# tinyio.net
KiCad netlist of a schematic drawn in EAGLE
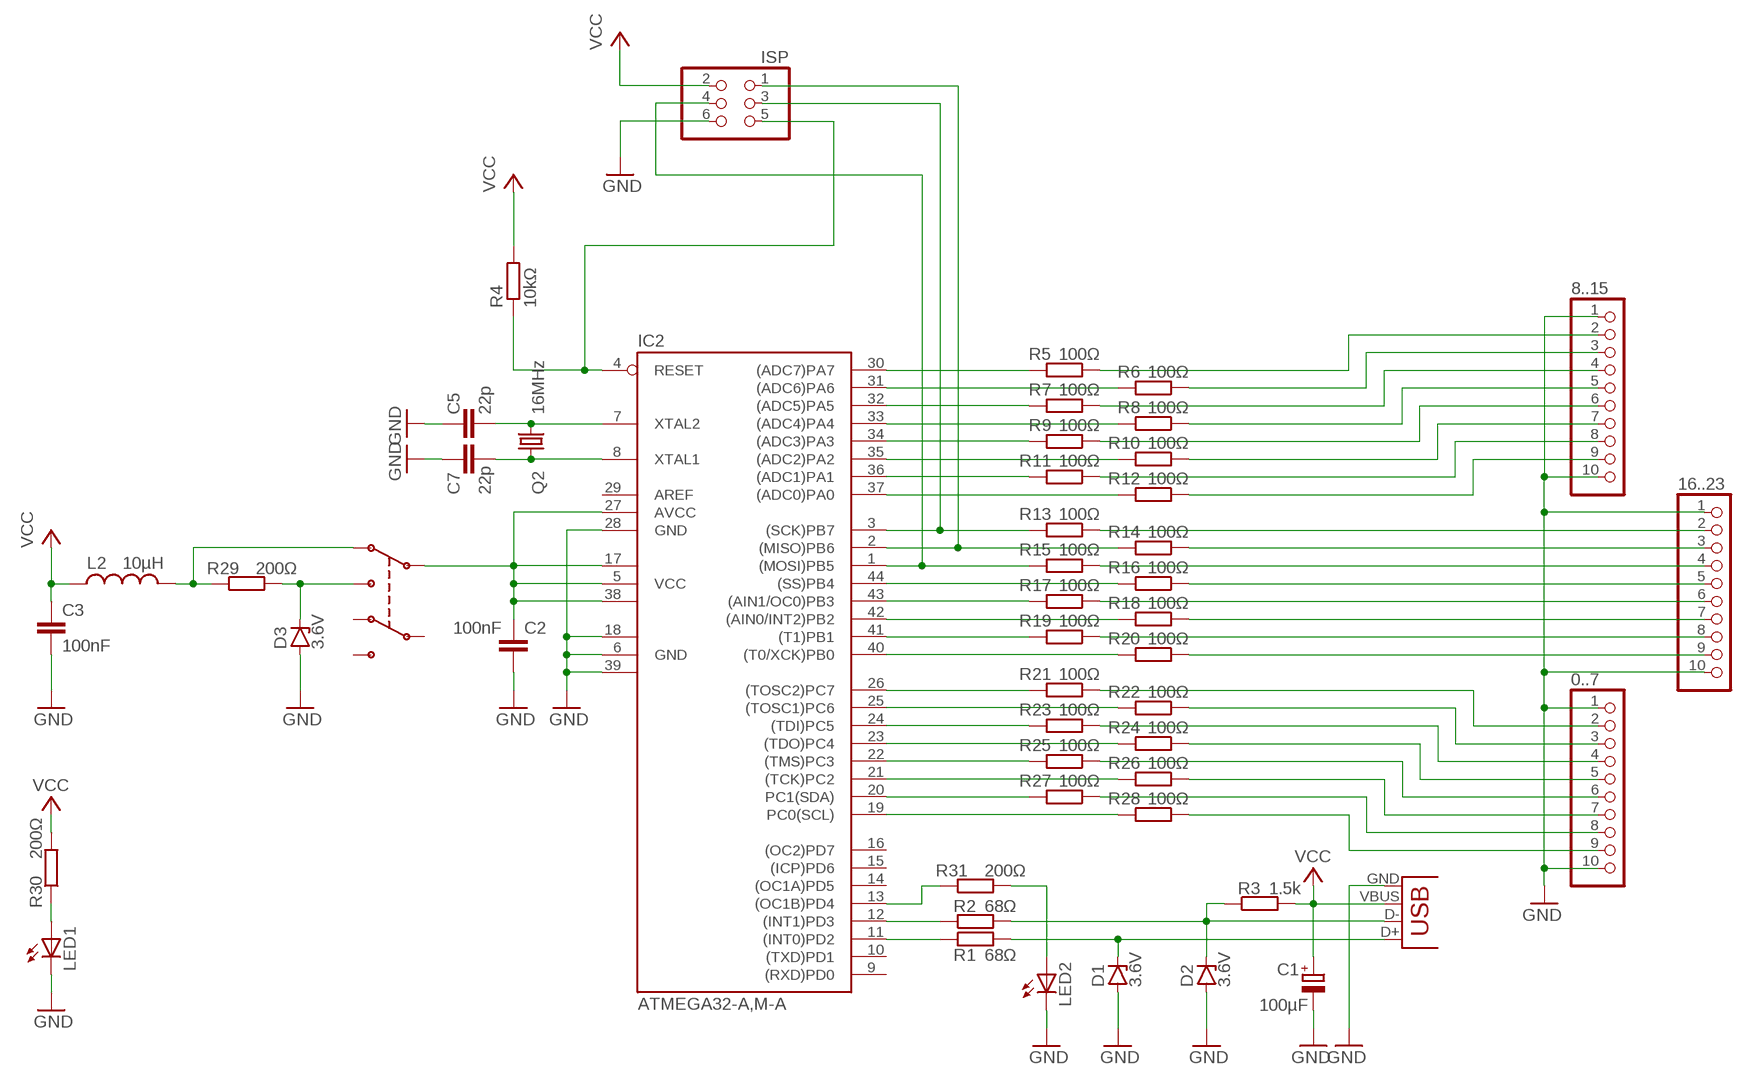
[diagram p0: schematic, sheet 1]

(export (version "E")
  (design (tool "Eeschema 10.0.6"))
  (components
    (comp (ref "0..7")
      (value "PINHD-1X10_2.54-SMD")
      (footprint "eagle-import:1X10SMD")
      (libsource (lib "eagle-import") (part "PINHD-1X10_2.54-SMD"))
    )
    (comp (ref "8..15")
      (value "PINHD-1X10_2.54-SMD")
      (footprint "eagle-import:1X10SMD")
      (libsource (lib "eagle-import") (part "PINHD-1X10_2.54-SMD"))
    )
    (comp (ref "16..23")
      (value "PINHD-1X10_2.54-SMD")
      (footprint "eagle-import:1X10SMD")
      (libsource (lib "eagle-import") (part "PINHD-1X10_2.54-SMD"))
    )
    (comp (ref "C1")
      (value "100µF")
      (footprint "eagle-import:D_7343-31R")
      (libsource (lib "eagle-import") (part "CPOL-EUD/7343-31R"))
    )
    (comp (ref "C2")
      (value "100nF")
      (footprint "eagle-import:C1206")
      (libsource (lib "eagle-import") (part "C-EUC1206"))
    )
    (comp (ref "C3")
      (value "100nF")
      (footprint "eagle-import:C1206")
      (libsource (lib "eagle-import") (part "C-EUC1206"))
    )
    (comp (ref "C5")
      (value "22p")
      (footprint "eagle-import:C1206")
      (libsource (lib "eagle-import") (part "C-EUC1206"))
    )
    (comp (ref "C7")
      (value "22p")
      (footprint "eagle-import:C1206")
      (libsource (lib "eagle-import") (part "C-EUC1206"))
    )
    (comp (ref "D1")
      (value "3.6V")
      (footprint "eagle-import:DIODE-ZENER-0805")
      (libsource (lib "eagle-import") (part "DIODE-ZENER-0804"))
    )
    (comp (ref "D2")
      (value "3.6V")
      (footprint "eagle-import:DIODE-ZENER-0805")
      (libsource (lib "eagle-import") (part "DIODE-ZENER-0804"))
    )
    (comp (ref "D3")
      (value "3.6V")
      (footprint "eagle-import:DIODE-ZENER-0805")
      (libsource (lib "eagle-import") (part "DIODE-ZENER-0804"))
    )
    (comp (ref "IC2")
      (value "ATMEGA32-A,M-A")
      (footprint "eagle-import:TQFP44")
      (fields (field (name "MPN") "ATMEGA32-16AU"))
      (libsource (lib "eagle-import") (part "ATMEGA32-A,M-A"))
    )
    (comp (ref "ISP")
      (value "PINHD-2X3_2.54-SMD")
      (footprint "eagle-import:2X03SMD")
      (libsource (lib "eagle-import") (part "PINHD-2X3_2.54-SMD"))
    )
    (comp (ref "L2")
      (value "10µH")
      (footprint "eagle-import:L1812")
      (libsource (lib "eagle-import") (part "L-USL1812"))
    )
    (comp (ref "LED1")
      (value "LEDCHIPLED_0805")
      (footprint "eagle-import:CHIPLED_0805")
      (libsource (lib "eagle-import") (part "LEDCHIPLED_0805"))
    )
    (comp (ref "LED2")
      (value "LEDCHIPLED_0805")
      (footprint "eagle-import:CHIPLED_0805")
      (libsource (lib "eagle-import") (part "LEDCHIPLED_0805"))
    )
    (comp (ref "Q2")
      (value "16MHz")
      (footprint "eagle-import:CSM-7X-DU")
      (libsource (lib "eagle-import") (part "CSM-7X-DU"))
    )
    (comp (ref "R1")
      (value "68Ω")
      (footprint "eagle-import:R1206")
      (libsource (lib "eagle-import") (part "R-EU_R1206"))
    )
    (comp (ref "R2")
      (value "68Ω")
      (footprint "eagle-import:R1206")
      (libsource (lib "eagle-import") (part "R-EU_R1206"))
    )
    (comp (ref "R3")
      (value "1.5k")
      (footprint "eagle-import:R1206")
      (libsource (lib "eagle-import") (part "R-EU_R1206"))
    )
    (comp (ref "R4")
      (value "10kΩ")
      (footprint "eagle-import:R0603")
      (libsource (lib "eagle-import") (part "R-EU_R0603"))
    )
    (comp (ref "R5")
      (value "100Ω")
      (footprint "eagle-import:R0603")
      (libsource (lib "eagle-import") (part "R-EU_R0603"))
    )
    (comp (ref "R6")
      (value "100Ω")
      (footprint "eagle-import:R0603")
      (libsource (lib "eagle-import") (part "R-EU_R0603"))
    )
    (comp (ref "R7")
      (value "100Ω")
      (footprint "eagle-import:R0603")
      (libsource (lib "eagle-import") (part "R-EU_R0603"))
    )
    (comp (ref "R8")
      (value "100Ω")
      (footprint "eagle-import:R0603")
      (libsource (lib "eagle-import") (part "R-EU_R0603"))
    )
    (comp (ref "R9")
      (value "100Ω")
      (footprint "eagle-import:R0603")
      (libsource (lib "eagle-import") (part "R-EU_R0603"))
    )
    (comp (ref "R10")
      (value "100Ω")
      (footprint "eagle-import:R0603")
      (libsource (lib "eagle-import") (part "R-EU_R0603"))
    )
    (comp (ref "R11")
      (value "100Ω")
      (footprint "eagle-import:R0603")
      (libsource (lib "eagle-import") (part "R-EU_R0603"))
    )
    (comp (ref "R12")
      (value "100Ω")
      (footprint "eagle-import:R0603")
      (libsource (lib "eagle-import") (part "R-EU_R0603"))
    )
    (comp (ref "R13")
      (value "100Ω")
      (footprint "eagle-import:R0603")
      (libsource (lib "eagle-import") (part "R-EU_R0603"))
    )
    (comp (ref "R14")
      (value "100Ω")
      (footprint "eagle-import:R0603")
      (libsource (lib "eagle-import") (part "R-EU_R0603"))
    )
    (comp (ref "R15")
      (value "100Ω")
      (footprint "eagle-import:R0603")
      (libsource (lib "eagle-import") (part "R-EU_R0603"))
    )
    (comp (ref "R16")
      (value "100Ω")
      (footprint "eagle-import:R0603")
      (libsource (lib "eagle-import") (part "R-EU_R0603"))
    )
    (comp (ref "R17")
      (value "100Ω")
      (footprint "eagle-import:R0603")
      (libsource (lib "eagle-import") (part "R-EU_R0603"))
    )
    (comp (ref "R18")
      (value "100Ω")
      (footprint "eagle-import:R0603")
      (libsource (lib "eagle-import") (part "R-EU_R0603"))
    )
    (comp (ref "R19")
      (value "100Ω")
      (footprint "eagle-import:R0603")
      (libsource (lib "eagle-import") (part "R-EU_R0603"))
    )
    (comp (ref "R20")
      (value "100Ω")
      (footprint "eagle-import:R0603")
      (libsource (lib "eagle-import") (part "R-EU_R0603"))
    )
    (comp (ref "R21")
      (value "100Ω")
      (footprint "eagle-import:R0603")
      (libsource (lib "eagle-import") (part "R-EU_R0603"))
    )
    (comp (ref "R22")
      (value "100Ω")
      (footprint "eagle-import:R0603")
      (libsource (lib "eagle-import") (part "R-EU_R0603"))
    )
    (comp (ref "R23")
      (value "100Ω")
      (footprint "eagle-import:R0603")
      (libsource (lib "eagle-import") (part "R-EU_R0603"))
    )
    (comp (ref "R24")
      (value "100Ω")
      (footprint "eagle-import:R0603")
      (libsource (lib "eagle-import") (part "R-EU_R0603"))
    )
    (comp (ref "R25")
      (value "100Ω")
      (footprint "eagle-import:R0603")
      (libsource (lib "eagle-import") (part "R-EU_R0603"))
    )
    (comp (ref "R26")
      (value "100Ω")
      (footprint "eagle-import:R0603")
      (libsource (lib "eagle-import") (part "R-EU_R0603"))
    )
    (comp (ref "R27")
      (value "100Ω")
      (footprint "eagle-import:R0603")
      (libsource (lib "eagle-import") (part "R-EU_R0603"))
    )
    (comp (ref "R28")
      (value "100Ω")
      (footprint "eagle-import:R0603")
      (libsource (lib "eagle-import") (part "R-EU_R0603"))
    )
    (comp (ref "R29")
      (value "200Ω")
      (footprint "eagle-import:R1206")
      (libsource (lib "eagle-import") (part "R-EU_R1206"))
    )
    (comp (ref "R30")
      (value "200Ω")
      (footprint "eagle-import:R1206")
      (libsource (lib "eagle-import") (part "R-EU_R1206"))
    )
    (comp (ref "R31")
      (value "200Ω")
      (footprint "eagle-import:R1206")
      (libsource (lib "eagle-import") (part "R-EU_R1206"))
    )
    (comp (ref "U$3")
      (value "SWTICH-DPDT1")
      (footprint "eagle-import:SWITCH-TOP-DPDT")
      (libsource (lib "eagle-import") (part "SWTICH-DPDT1"))
    )
    (comp (ref "X1")
      (value "USBSMD")
      (footprint "eagle-import:USB-MINIB")
      (libsource (lib "eagle-import") (part "USBSMD"))
    )
  )
  (nets
    (net (code "1") (name "GND") (class "Default")
      (node (ref "0..7") (pin "1") (pinfunction "1_1") (pintype "passive"))
      (node (ref "0..7") (pin "10") (pinfunction "10_10") (pintype "passive"))
      (node (ref "16..23") (pin "1") (pinfunction "1_1") (pintype "passive"))
      (node (ref "16..23") (pin "10") (pinfunction "10_10") (pintype "passive"))
      (node (ref "8..15") (pin "1") (pinfunction "1_1") (pintype "passive"))
      (node (ref "8..15") (pin "10") (pinfunction "10_10") (pintype "passive"))
      (node (ref "C1") (pin "-") (pinfunction "-_-") (pintype "passive"))
      (node (ref "C2") (pin "2") (pinfunction "2_2") (pintype "passive"))
      (node (ref "C3") (pin "2") (pinfunction "2_2") (pintype "passive"))
      (node (ref "C5") (pin "1") (pinfunction "1_1") (pintype "passive"))
      (node (ref "C7") (pin "1") (pinfunction "1_1") (pintype "passive"))
      (node (ref "D1") (pin "A") (pinfunction "A_A") (pintype "passive"))
      (node (ref "D2") (pin "A") (pinfunction "A_A") (pintype "passive"))
      (node (ref "D3") (pin "A") (pinfunction "A_A") (pintype "passive"))
      (node (ref "IC2") (pin "18") (pinfunction "GND1_18") (pintype "power_in"))
      (node (ref "IC2") (pin "28") (pinfunction "GND_28") (pintype "power_in"))
      (node (ref "IC2") (pin "39") (pinfunction "GND2_39") (pintype "power_in"))
      (node (ref "IC2") (pin "6") (pinfunction "GND_6") (pintype "power_in"))
      (node (ref "ISP") (pin "6") (pinfunction "6_6") (pintype "passive"))
      (node (ref "LED1") (pin "C") (pinfunction "C_C") (pintype "passive"))
      (node (ref "LED2") (pin "C") (pinfunction "C_C") (pintype "passive"))
      (node (ref "X1") (pin "GND") (pinfunction "GND_GND") (pintype "bidirectional"))
    )
    (net (code "2") (name "Net-(0..7-Pad2)") (class "Default")
      (node (ref "0..7") (pin "2") (pinfunction "2_2") (pintype "passive"))
      (node (ref "R21") (pin "1") (pinfunction "1_1") (pintype "passive"))
    )
    (net (code "3") (name "Net-(0..7-Pad3)") (class "Default")
      (node (ref "0..7") (pin "3") (pinfunction "3_3") (pintype "passive"))
      (node (ref "R22") (pin "1") (pinfunction "1_1") (pintype "passive"))
    )
    (net (code "4") (name "Net-(0..7-Pad4)") (class "Default")
      (node (ref "0..7") (pin "4") (pinfunction "4_4") (pintype "passive"))
      (node (ref "R23") (pin "1") (pinfunction "1_1") (pintype "passive"))
    )
    (net (code "5") (name "Net-(0..7-Pad5)") (class "Default")
      (node (ref "0..7") (pin "5") (pinfunction "5_5") (pintype "passive"))
      (node (ref "R24") (pin "1") (pinfunction "1_1") (pintype "passive"))
    )
    (net (code "6") (name "Net-(0..7-Pad6)") (class "Default")
      (node (ref "0..7") (pin "6") (pinfunction "6_6") (pintype "passive"))
      (node (ref "R25") (pin "1") (pinfunction "1_1") (pintype "passive"))
    )
    (net (code "7") (name "Net-(0..7-Pad7)") (class "Default")
      (node (ref "0..7") (pin "7") (pinfunction "7_7") (pintype "passive"))
      (node (ref "R26") (pin "1") (pinfunction "1_1") (pintype "passive"))
    )
    (net (code "8") (name "Net-(0..7-Pad8)") (class "Default")
      (node (ref "0..7") (pin "8") (pinfunction "8_8") (pintype "passive"))
      (node (ref "R27") (pin "1") (pinfunction "1_1") (pintype "passive"))
    )
    (net (code "9") (name "Net-(0..7-Pad9)") (class "Default")
      (node (ref "0..7") (pin "9") (pinfunction "9_9") (pintype "passive"))
      (node (ref "R28") (pin "1") (pinfunction "1_1") (pintype "passive"))
    )
    (net (code "10") (name "Net-(8..15-Pad2)") (class "Default")
      (node (ref "8..15") (pin "2") (pinfunction "2_2") (pintype "passive"))
      (node (ref "R5") (pin "1") (pinfunction "1_1") (pintype "passive"))
    )
    (net (code "11") (name "Net-(8..15-Pad3)") (class "Default")
      (node (ref "8..15") (pin "3") (pinfunction "3_3") (pintype "passive"))
      (node (ref "R6") (pin "1") (pinfunction "1_1") (pintype "passive"))
    )
    (net (code "12") (name "Net-(8..15-Pad4)") (class "Default")
      (node (ref "8..15") (pin "4") (pinfunction "4_4") (pintype "passive"))
      (node (ref "R7") (pin "1") (pinfunction "1_1") (pintype "passive"))
    )
    (net (code "13") (name "Net-(8..15-Pad5)") (class "Default")
      (node (ref "8..15") (pin "5") (pinfunction "5_5") (pintype "passive"))
      (node (ref "R8") (pin "1") (pinfunction "1_1") (pintype "passive"))
    )
    (net (code "14") (name "Net-(8..15-Pad6)") (class "Default")
      (node (ref "8..15") (pin "6") (pinfunction "6_6") (pintype "passive"))
      (node (ref "R9") (pin "1") (pinfunction "1_1") (pintype "passive"))
    )
    (net (code "15") (name "Net-(8..15-Pad7)") (class "Default")
      (node (ref "8..15") (pin "7") (pinfunction "7_7") (pintype "passive"))
      (node (ref "R10") (pin "1") (pinfunction "1_1") (pintype "passive"))
    )
    (net (code "16") (name "Net-(8..15-Pad8)") (class "Default")
      (node (ref "8..15") (pin "8") (pinfunction "8_8") (pintype "passive"))
      (node (ref "R11") (pin "1") (pinfunction "1_1") (pintype "passive"))
    )
    (net (code "17") (name "Net-(8..15-Pad9)") (class "Default")
      (node (ref "8..15") (pin "9") (pinfunction "9_9") (pintype "passive"))
      (node (ref "R12") (pin "1") (pinfunction "1_1") (pintype "passive"))
    )
    (net (code "18") (name "Net-(16..23-Pad2)") (class "Default")
      (node (ref "16..23") (pin "2") (pinfunction "2_2") (pintype "passive"))
      (node (ref "R13") (pin "1") (pinfunction "1_1") (pintype "passive"))
    )
    (net (code "19") (name "Net-(16..23-Pad3)") (class "Default")
      (node (ref "16..23") (pin "3") (pinfunction "3_3") (pintype "passive"))
      (node (ref "R14") (pin "1") (pinfunction "1_1") (pintype "passive"))
    )
    (net (code "20") (name "Net-(16..23-Pad4)") (class "Default")
      (node (ref "16..23") (pin "4") (pinfunction "4_4") (pintype "passive"))
      (node (ref "R15") (pin "1") (pinfunction "1_1") (pintype "passive"))
    )
    (net (code "21") (name "Net-(16..23-Pad5)") (class "Default")
      (node (ref "16..23") (pin "5") (pinfunction "5_5") (pintype "passive"))
      (node (ref "R16") (pin "1") (pinfunction "1_1") (pintype "passive"))
    )
    (net (code "22") (name "Net-(16..23-Pad6)") (class "Default")
      (node (ref "16..23") (pin "6") (pinfunction "6_6") (pintype "passive"))
      (node (ref "R17") (pin "1") (pinfunction "1_1") (pintype "passive"))
    )
    (net (code "23") (name "Net-(16..23-Pad7)") (class "Default")
      (node (ref "16..23") (pin "7") (pinfunction "7_7") (pintype "passive"))
      (node (ref "R18") (pin "1") (pinfunction "1_1") (pintype "passive"))
    )
    (net (code "24") (name "Net-(16..23-Pad8)") (class "Default")
      (node (ref "16..23") (pin "8") (pinfunction "8_8") (pintype "passive"))
      (node (ref "R19") (pin "1") (pinfunction "1_1") (pintype "passive"))
    )
    (net (code "25") (name "Net-(16..23-Pad9)") (class "Default")
      (node (ref "16..23") (pin "9") (pinfunction "9_9") (pintype "passive"))
      (node (ref "R20") (pin "1") (pinfunction "1_1") (pintype "passive"))
    )
    (net (code "26") (name "Net-(D1-C)") (class "Default")
      (node (ref "D1") (pin "K") (pinfunction "C_K") (pintype "passive"))
      (node (ref "R1") (pin "2") (pinfunction "2_2") (pintype "passive"))
      (node (ref "X1") (pin "D+") (pinfunction "D+_D+") (pintype "bidirectional"))
    )
    (net (code "27") (name "Net-(D2-C)") (class "Default")
      (node (ref "D2") (pin "K") (pinfunction "C_K") (pintype "passive"))
      (node (ref "R2") (pin "2") (pinfunction "2_2") (pintype "passive"))
      (node (ref "R3") (pin "1") (pinfunction "1_1") (pintype "passive"))
      (node (ref "X1") (pin "D-") (pinfunction "D-_D-") (pintype "bidirectional"))
    )
    (net (code "28") (name "Net-(D3-C)") (class "Default")
      (node (ref "D3") (pin "K") (pinfunction "C_K") (pintype "passive"))
      (node (ref "R29") (pin "2") (pinfunction "2_2") (pintype "passive"))
      (node (ref "U$3") (pin "1NO") (pinfunction "1NO_1NO") (pintype "bidirectional"))
    )
    (net (code "29") (name "Net-(IC2-(ADC0)PA0)") (class "Default")
      (node (ref "IC2") (pin "37") (pinfunction "(ADC0)PA0_37") (pintype "bidirectional"))
      (node (ref "R12") (pin "2") (pinfunction "2_2") (pintype "passive"))
    )
    (net (code "30") (name "Net-(IC2-(ADC1)PA1)") (class "Default")
      (node (ref "IC2") (pin "36") (pinfunction "(ADC1)PA1_36") (pintype "bidirectional"))
      (node (ref "R11") (pin "2") (pinfunction "2_2") (pintype "passive"))
    )
    (net (code "31") (name "Net-(IC2-(ADC2)PA2)") (class "Default")
      (node (ref "IC2") (pin "35") (pinfunction "(ADC2)PA2_35") (pintype "bidirectional"))
      (node (ref "R10") (pin "2") (pinfunction "2_2") (pintype "passive"))
    )
    (net (code "32") (name "Net-(IC2-(ADC3)PA3)") (class "Default")
      (node (ref "IC2") (pin "34") (pinfunction "(ADC3)PA3_34") (pintype "bidirectional"))
      (node (ref "R9") (pin "2") (pinfunction "2_2") (pintype "passive"))
    )
    (net (code "33") (name "Net-(IC2-(ADC4)PA4)") (class "Default")
      (node (ref "IC2") (pin "33") (pinfunction "(ADC4)PA4_33") (pintype "bidirectional"))
      (node (ref "R8") (pin "2") (pinfunction "2_2") (pintype "passive"))
    )
    (net (code "34") (name "Net-(IC2-(ADC5)PA5)") (class "Default")
      (node (ref "IC2") (pin "32") (pinfunction "(ADC5)PA5_32") (pintype "bidirectional"))
      (node (ref "R7") (pin "2") (pinfunction "2_2") (pintype "passive"))
    )
    (net (code "35") (name "Net-(IC2-(ADC6)PA6)") (class "Default")
      (node (ref "IC2") (pin "31") (pinfunction "(ADC6)PA6_31") (pintype "bidirectional"))
      (node (ref "R6") (pin "2") (pinfunction "2_2") (pintype "passive"))
    )
    (net (code "36") (name "Net-(IC2-(ADC7)PA7)") (class "Default")
      (node (ref "IC2") (pin "30") (pinfunction "(ADC7)PA7_30") (pintype "bidirectional"))
      (node (ref "R5") (pin "2") (pinfunction "2_2") (pintype "passive"))
    )
    (net (code "37") (name "Net-(IC2-(AIN0{slash}INT2)PB2)") (class "Default")
      (node (ref "IC2") (pin "42") (pinfunction "(AIN0/INT2)PB2_42") (pintype "bidirectional"))
      (node (ref "R18") (pin "2") (pinfunction "2_2") (pintype "passive"))
    )
    (net (code "38") (name "Net-(IC2-(AIN1{slash}OC0)PB3)") (class "Default")
      (node (ref "IC2") (pin "43") (pinfunction "(AIN1/OC0)PB3_43") (pintype "bidirectional"))
      (node (ref "R17") (pin "2") (pinfunction "2_2") (pintype "passive"))
    )
    (net (code "39") (name "Net-(IC2-(INT0)PD2)") (class "Default")
      (node (ref "IC2") (pin "11") (pinfunction "(INT0)PD2_11") (pintype "bidirectional"))
      (node (ref "R1") (pin "1") (pinfunction "1_1") (pintype "passive"))
    )
    (net (code "40") (name "Net-(IC2-(INT1)PD3)") (class "Default")
      (node (ref "IC2") (pin "12") (pinfunction "(INT1)PD3_12") (pintype "bidirectional"))
      (node (ref "R2") (pin "1") (pinfunction "1_1") (pintype "passive"))
    )
    (net (code "41") (name "Net-(IC2-(MISO)PB6)") (class "Default")
      (node (ref "IC2") (pin "2") (pinfunction "(MISO)PB6_2") (pintype "bidirectional"))
      (node (ref "ISP") (pin "1") (pinfunction "1_1") (pintype "passive"))
      (node (ref "R14") (pin "2") (pinfunction "2_2") (pintype "passive"))
    )
    (net (code "42") (name "Net-(IC2-(MOSI)PB5)") (class "Default")
      (node (ref "IC2") (pin "1") (pinfunction "(MOSI)PB5_1") (pintype "bidirectional"))
      (node (ref "ISP") (pin "4") (pinfunction "4_4") (pintype "passive"))
      (node (ref "R15") (pin "2") (pinfunction "2_2") (pintype "passive"))
    )
    (net (code "43") (name "Net-(IC2-(OC1B)PD4)") (class "Default")
      (node (ref "IC2") (pin "13") (pinfunction "(OC1B)PD4_13") (pintype "bidirectional"))
      (node (ref "R31") (pin "1") (pinfunction "1_1") (pintype "passive"))
    )
    (net (code "44") (name "Net-(IC2-(SCK)PB7)") (class "Default")
      (node (ref "IC2") (pin "3") (pinfunction "(SCK)PB7_3") (pintype "bidirectional"))
      (node (ref "ISP") (pin "3") (pinfunction "3_3") (pintype "passive"))
      (node (ref "R13") (pin "2") (pinfunction "2_2") (pintype "passive"))
    )
    (net (code "45") (name "Net-(IC2-(SS)PB4)") (class "Default")
      (node (ref "IC2") (pin "44") (pinfunction "(SS)PB4_44") (pintype "bidirectional"))
      (node (ref "R16") (pin "2") (pinfunction "2_2") (pintype "passive"))
    )
    (net (code "46") (name "Net-(IC2-(T0{slash}XCK)PB0)") (class "Default")
      (node (ref "IC2") (pin "40") (pinfunction "(T0/XCK)PB0_40") (pintype "bidirectional"))
      (node (ref "R20") (pin "2") (pinfunction "2_2") (pintype "passive"))
    )
    (net (code "47") (name "Net-(IC2-(T1)PB1)") (class "Default")
      (node (ref "IC2") (pin "41") (pinfunction "(T1)PB1_41") (pintype "bidirectional"))
      (node (ref "R19") (pin "2") (pinfunction "2_2") (pintype "passive"))
    )
    (net (code "48") (name "Net-(IC2-(TCK)PC2)") (class "Default")
      (node (ref "IC2") (pin "21") (pinfunction "(TCK)PC2_21") (pintype "bidirectional"))
      (node (ref "R26") (pin "2") (pinfunction "2_2") (pintype "passive"))
    )
    (net (code "49") (name "Net-(IC2-(TDI)PC5)") (class "Default")
      (node (ref "IC2") (pin "24") (pinfunction "(TDI)PC5_24") (pintype "bidirectional"))
      (node (ref "R23") (pin "2") (pinfunction "2_2") (pintype "passive"))
    )
    (net (code "50") (name "Net-(IC2-(TDO)PC4)") (class "Default")
      (node (ref "IC2") (pin "23") (pinfunction "(TDO)PC4_23") (pintype "bidirectional"))
      (node (ref "R24") (pin "2") (pinfunction "2_2") (pintype "passive"))
    )
    (net (code "51") (name "Net-(IC2-(TMS)PC3)") (class "Default")
      (node (ref "IC2") (pin "22") (pinfunction "(TMS)PC3_22") (pintype "bidirectional"))
      (node (ref "R25") (pin "2") (pinfunction "2_2") (pintype "passive"))
    )
    (net (code "52") (name "Net-(IC2-(TOSC1)PC6)") (class "Default")
      (node (ref "IC2") (pin "25") (pinfunction "(TOSC1)PC6_25") (pintype "bidirectional"))
      (node (ref "R22") (pin "2") (pinfunction "2_2") (pintype "passive"))
    )
    (net (code "53") (name "Net-(IC2-(TOSC2)PC7)") (class "Default")
      (node (ref "IC2") (pin "26") (pinfunction "(TOSC2)PC7_26") (pintype "bidirectional"))
      (node (ref "R21") (pin "2") (pinfunction "2_2") (pintype "passive"))
    )
    (net (code "54") (name "Net-(IC2-AVCC)") (class "Default")
      (node (ref "C2") (pin "1") (pinfunction "1_1") (pintype "passive"))
      (node (ref "IC2") (pin "17") (pinfunction "VCC1_17") (pintype "power_in"))
      (node (ref "IC2") (pin "27") (pinfunction "AVCC_27") (pintype "power_in"))
      (node (ref "IC2") (pin "38") (pinfunction "VCC2_38") (pintype "power_in"))
      (node (ref "IC2") (pin "5") (pinfunction "VCC_5") (pintype "power_in"))
      (node (ref "U$3") (pin "1") (pinfunction "1_1") (pintype "bidirectional"))
    )
    (net (code "55") (name "Net-(IC2-PC0(SCL))") (class "Default")
      (node (ref "IC2") (pin "19") (pinfunction "PC0(SCL)_19") (pintype "bidirectional"))
      (node (ref "R28") (pin "2") (pinfunction "2_2") (pintype "passive"))
    )
    (net (code "56") (name "Net-(IC2-PC1(SDA))") (class "Default")
      (node (ref "IC2") (pin "20") (pinfunction "PC1(SDA)_20") (pintype "bidirectional"))
      (node (ref "R27") (pin "2") (pinfunction "2_2") (pintype "passive"))
    )
    (net (code "57") (name "Net-(IC2-RESET)") (class "Default")
      (node (ref "IC2") (pin "4") (pinfunction "RESET_4") (pintype "input"))
      (node (ref "ISP") (pin "5") (pinfunction "5_5") (pintype "passive"))
      (node (ref "R4") (pin "1") (pinfunction "1_1") (pintype "passive"))
    )
    (net (code "58") (name "Net-(IC2-XTAL1)") (class "Default")
      (node (ref "C7") (pin "2") (pinfunction "2_2") (pintype "passive"))
      (node (ref "IC2") (pin "8") (pinfunction "XTAL1_8") (pintype "bidirectional"))
      (node (ref "Q2") (pin "1") (pinfunction "1_1") (pintype "passive"))
    )
    (net (code "59") (name "Net-(IC2-XTAL2)") (class "Default")
      (node (ref "C5") (pin "2") (pinfunction "2_2") (pintype "passive"))
      (node (ref "IC2") (pin "7") (pinfunction "XTAL2_7") (pintype "bidirectional"))
      (node (ref "Q2") (pin "2") (pinfunction "2_2") (pintype "passive"))
    )
    (net (code "60") (name "Net-(L2-Pad1)") (class "Default")
      (node (ref "L2") (pin "1") (pinfunction "1_1") (pintype "passive"))
      (node (ref "R29") (pin "1") (pinfunction "1_1") (pintype "passive"))
      (node (ref "U$3") (pin "1NC") (pinfunction "1NC_1NC") (pintype "bidirectional"))
    )
    (net (code "61") (name "Net-(LED1-PadA)") (class "Default")
      (node (ref "LED1") (pin "A") (pinfunction "A_A") (pintype "passive"))
      (node (ref "R30") (pin "1") (pinfunction "1_1") (pintype "passive"))
    )
    (net (code "62") (name "Net-(LED2-PadA)") (class "Default")
      (node (ref "LED2") (pin "A") (pinfunction "A_A") (pintype "passive"))
      (node (ref "R31") (pin "2") (pinfunction "2_2") (pintype "passive"))
    )
    (net (code "63") (name "VCC") (class "Default")
      (node (ref "C1") (pin "+") (pinfunction "+_+") (pintype "passive"))
      (node (ref "C3") (pin "1") (pinfunction "1_1") (pintype "passive"))
      (node (ref "ISP") (pin "2") (pinfunction "2_2") (pintype "passive"))
      (node (ref "L2") (pin "2") (pinfunction "2_2") (pintype "passive"))
      (node (ref "R3") (pin "2") (pinfunction "2_2") (pintype "passive"))
      (node (ref "R30") (pin "2") (pinfunction "2_2") (pintype "passive"))
      (node (ref "R4") (pin "2") (pinfunction "2_2") (pintype "passive"))
      (node (ref "X1") (pin "VBUS") (pinfunction "VBUS_VBUS") (pintype "bidirectional"))
    )
    (net (code "64") (name "unconnected-(IC2-(ICP)PD6-Pad15)") (class "Default")
      (node (ref "IC2") (pin "15") (pinfunction "(ICP)PD6_15") (pintype "bidirectional"))
    )
    (net (code "65") (name "unconnected-(IC2-(OC1A)PD5-Pad14)") (class "Default")
      (node (ref "IC2") (pin "14") (pinfunction "(OC1A)PD5_14") (pintype "bidirectional"))
    )
    (net (code "66") (name "unconnected-(IC2-(OC2)PD7-Pad16)") (class "Default")
      (node (ref "IC2") (pin "16") (pinfunction "(OC2)PD7_16") (pintype "bidirectional"))
    )
    (net (code "67") (name "unconnected-(IC2-(RXD)PD0-Pad9)") (class "Default")
      (node (ref "IC2") (pin "9") (pinfunction "(RXD)PD0_9") (pintype "bidirectional"))
    )
    (net (code "68") (name "unconnected-(IC2-(TXD)PD1-Pad10)") (class "Default")
      (node (ref "IC2") (pin "10") (pinfunction "(TXD)PD1_10") (pintype "bidirectional"))
    )
    (net (code "69") (name "unconnected-(IC2-AREF-Pad29)") (class "Default")
      (node (ref "IC2") (pin "29") (pinfunction "AREF_29") (pintype "passive"))
    )
    (net (code "70") (name "unconnected-(U$3-Pad2)") (class "Default")
      (node (ref "U$3") (pin "2") (pinfunction "2_2") (pintype "bidirectional"))
    )
    (net (code "71") (name "unconnected-(U$3-Pad2NC)") (class "Default")
      (node (ref "U$3") (pin "2NC") (pinfunction "2NC_2NC") (pintype "bidirectional"))
    )
    (net (code "72") (name "unconnected-(U$3-Pad2NO)") (class "Default")
      (node (ref "U$3") (pin "2NO") (pinfunction "2NO_2NO") (pintype "bidirectional"))
    )
  )
)
